# MCU.net
KiCad netlist of a schematic drawn in Altium Designer
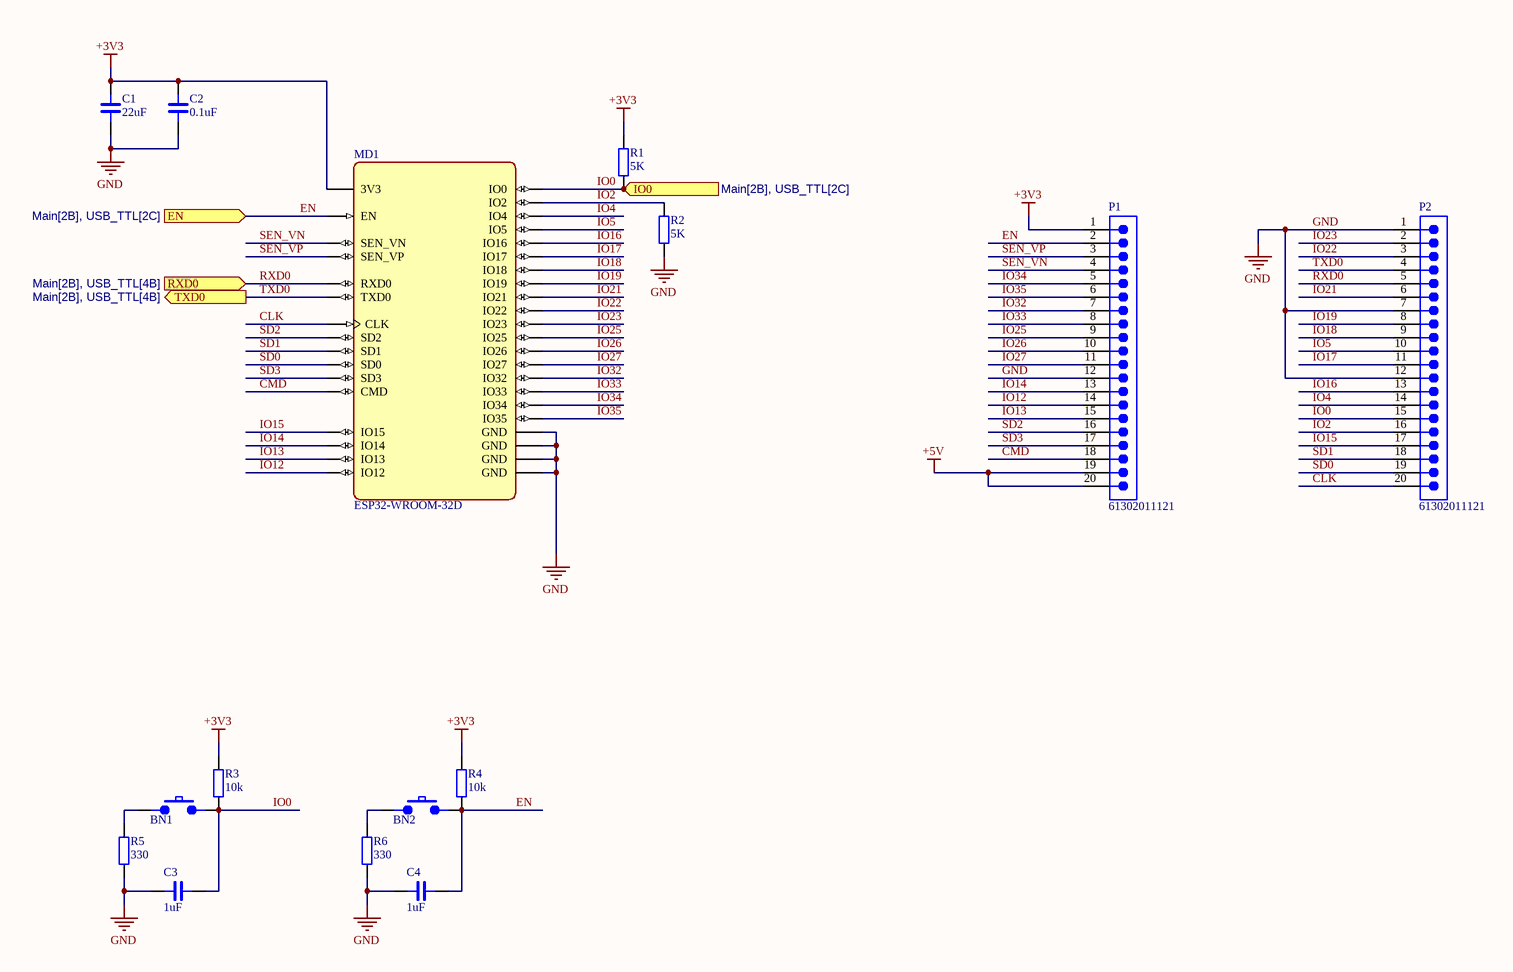
[diagram p0: MCU.SchDoc]

(export (version "E")
  (design (tool "Eeschema 10.0.6"))
  (components
    (comp (ref "BN1")
      (value "SKRPABE010")
      (footprint "BTN_SKRPABE010")
      (description "3.2mm 2.5mm button 50mA Brick SPST 16V SMD Tactile Switches")
      (fields (field (name "JLCPCB PART") "?"))
      (libsource (lib "FIC_OAL") (part "BTN_SKRPABE010"))
    )
    (comp (ref "BN2")
      (value "SKRPABE010")
      (footprint "BTN_SKRPABE010")
      (description "3.2mm 2.5mm button 50mA Brick SPST 16V SMD Tactile Switches")
      (fields (field (name "JLCPCB PART") "?"))
      (libsource (lib "FIC_OAL") (part "BTN_SKRPABE010"))
    )
    (comp (ref "C1")
      (value "22uF")
      (footprint "CAP_0603")
      (description "0603 Multilayer Ceramic Capacitors MLCC - SMD/SMT ROHS")
      (fields (field (name "LCSC PART") "?"))
      (libsource (lib "FIC_OAL") (part "CAP_0603"))
    )
    (comp (ref "C2")
      (value "0.1uF")
      (footprint "CAP_0603")
      (description "0603 Multilayer Ceramic Capacitors MLCC - SMD/SMT ROHS")
      (fields (field (name "LCSC PART") "?"))
      (libsource (lib "FIC_OAL") (part "CAP_0603"))
    )
    (comp (ref "C3")
      (value "1uF")
      (footprint "CAP_0603")
      (description "0603 Multilayer Ceramic Capacitors MLCC - SMD/SMT ROHS")
      (fields (field (name "LCSC PART") "?"))
      (libsource (lib "FIC_OAL") (part "CAP_0603"))
    )
    (comp (ref "C4")
      (value "1uF")
      (footprint "CAP_0603")
      (description "0603 Multilayer Ceramic Capacitors MLCC - SMD/SMT ROHS")
      (fields (field (name "LCSC PART") "?"))
      (libsource (lib "FIC_OAL") (part "CAP_0603"))
    )
    (comp (ref "MD1")
      (value "ESP32-WROOM-32D")
      (footprint "MD_ESP32_WROOM_D")
      (description "core ESP32-D0WD, 32Mbits, 3.3V, 40Mhz, onboard antenna")
      (fields (field (name "MRF. PART") "?"))
      (libsource (lib "FIC_OAL") (part "MD_ESP32_WROOM_D"))
    )
    (comp (ref "P1")
      (value "61302011121")
      (footprint "61302011121")
      (libsource (lib "Altium Content Vault") (part "Header_Male_1R_20P"))
    )
    (comp (ref "P2")
      (value "61302011121")
      (footprint "61302011121")
      (libsource (lib "Altium Content Vault") (part "Header_Male_1R_20P"))
    )
    (comp (ref "R1")
      (value "5K")
      (footprint "RES_0603")
      (description "0603 Thick Film Resistor - Surface Mount ROHS")
      (fields (field (name "MFR. PART") "?"))
      (libsource (lib "FIC_OAL") (part "RES_0603"))
    )
    (comp (ref "R2")
      (value "5K")
      (footprint "RES_0603")
      (description "0603 Thick Film Resistor - Surface Mount ROHS")
      (fields (field (name "MFR. PART") "?"))
      (libsource (lib "FIC_OAL") (part "RES_0603"))
    )
    (comp (ref "R3")
      (value "10k")
      (footprint "RES_0603")
      (description "0603 Thick Film Resistor - Surface Mount ROHS")
      (fields (field (name "MFR. PART") "?"))
      (libsource (lib "FIC_OAL") (part "RES_0603"))
    )
    (comp (ref "R4")
      (value "10k")
      (footprint "RES_0603")
      (description "0603 Thick Film Resistor - Surface Mount ROHS")
      (fields (field (name "MFR. PART") "?"))
      (libsource (lib "FIC_OAL") (part "RES_0603"))
    )
    (comp (ref "R5")
      (value "330")
      (footprint "RES_0603")
      (description "0603 Thick Film Resistor - Surface Mount ROHS")
      (fields (field (name "MFR. PART") "?"))
      (libsource (lib "FIC_OAL") (part "RES_0603"))
    )
    (comp (ref "R6")
      (value "330")
      (footprint "RES_0603")
      (description "0603 Thick Film Resistor - Surface Mount ROHS")
      (fields (field (name "MFR. PART") "?"))
      (libsource (lib "FIC_OAL") (part "RES_0603"))
    )
  )
  (nets
    (net (code "1") (name "+3V3") (class "Default")
      (node (ref "C1") (pin "2") (pinfunction "2_2") (pintype "passive"))
      (node (ref "C2") (pin "2") (pinfunction "2_2") (pintype "passive"))
      (node (ref "MD1") (pin "2") (pinfunction "3V3_2") (pintype "passive"))
      (node (ref "P1") (pin "1") (pinfunction "1_1") (pintype "passive"))
      (node (ref "R1") (pin "2") (pinfunction "2_2") (pintype "passive"))
      (node (ref "R3") (pin "2") (pinfunction "2_2") (pintype "passive"))
      (node (ref "R4") (pin "2") (pinfunction "2_2") (pintype "passive"))
    )
    (net (code "2") (name "+5V") (class "Default")
      (node (ref "P1") (pin "19") (pinfunction "19_19") (pintype "passive"))
      (node (ref "P1") (pin "20") (pinfunction "20_20") (pintype "passive"))
    )
    (net (code "3") (name "/CLK") (class "Default")
      (node (ref "MD1") (pin "20") (pinfunction "CLK_20") (pintype "input"))
      (node (ref "P2") (pin "20") (pinfunction "20_20") (pintype "passive"))
    )
    (net (code "4") (name "/CMD") (class "Default")
      (node (ref "MD1") (pin "19") (pinfunction "CMD_19") (pintype "bidirectional"))
      (node (ref "P1") (pin "18") (pinfunction "18_18") (pintype "passive"))
    )
    (net (code "5") (name "/EN") (class "Default")
      (node (ref "BN2") (pin "34") (pinfunction "34_34") (pintype "passive"))
      (node (ref "C4") (pin "2") (pinfunction "2_2") (pintype "passive"))
      (node (ref "MD1") (pin "3") (pinfunction "EN_3") (pintype "input"))
      (node (ref "P1") (pin "2") (pinfunction "2_2") (pintype "passive"))
      (node (ref "R4") (pin "1") (pinfunction "1_1") (pintype "passive"))
    )
    (net (code "6") (name "/IO0") (class "Default")
      (node (ref "BN1") (pin "34") (pinfunction "34_34") (pintype "passive"))
      (node (ref "C3") (pin "2") (pinfunction "2_2") (pintype "passive"))
      (node (ref "MD1") (pin "25") (pinfunction "IO0_25") (pintype "bidirectional"))
      (node (ref "P2") (pin "15") (pinfunction "15_15") (pintype "passive"))
      (node (ref "R1") (pin "1") (pinfunction "1_1") (pintype "passive"))
      (node (ref "R3") (pin "1") (pinfunction "1_1") (pintype "passive"))
    )
    (net (code "7") (name "/IO2") (class "Default")
      (node (ref "MD1") (pin "24") (pinfunction "IO2_24") (pintype "bidirectional"))
      (node (ref "P2") (pin "16") (pinfunction "16_16") (pintype "passive"))
      (node (ref "R2") (pin "2") (pinfunction "2_2") (pintype "passive"))
    )
    (net (code "8") (name "/IO4") (class "Default")
      (node (ref "MD1") (pin "26") (pinfunction "IO4_26") (pintype "bidirectional"))
      (node (ref "P2") (pin "14") (pinfunction "14_14") (pintype "passive"))
    )
    (net (code "9") (name "/IO5") (class "Default")
      (node (ref "MD1") (pin "29") (pinfunction "IO5_29") (pintype "bidirectional"))
      (node (ref "P2") (pin "10") (pinfunction "10_10") (pintype "passive"))
    )
    (net (code "10") (name "/IO12") (class "Default")
      (node (ref "MD1") (pin "14") (pinfunction "IO12_14") (pintype "bidirectional"))
      (node (ref "P1") (pin "14") (pinfunction "14_14") (pintype "passive"))
    )
    (net (code "11") (name "/IO13") (class "Default")
      (node (ref "MD1") (pin "16") (pinfunction "IO13_16") (pintype "bidirectional"))
      (node (ref "P1") (pin "15") (pinfunction "15_15") (pintype "passive"))
    )
    (net (code "12") (name "/IO14") (class "Default")
      (node (ref "MD1") (pin "13") (pinfunction "IO14_13") (pintype "bidirectional"))
      (node (ref "P1") (pin "13") (pinfunction "13_13") (pintype "passive"))
    )
    (net (code "13") (name "/IO15") (class "Default")
      (node (ref "MD1") (pin "23") (pinfunction "IO15_23") (pintype "bidirectional"))
      (node (ref "P2") (pin "17") (pinfunction "17_17") (pintype "passive"))
    )
    (net (code "14") (name "/IO16") (class "Default")
      (node (ref "MD1") (pin "27") (pinfunction "IO16_27") (pintype "bidirectional"))
      (node (ref "P2") (pin "13") (pinfunction "13_13") (pintype "passive"))
    )
    (net (code "15") (name "/IO17") (class "Default")
      (node (ref "MD1") (pin "28") (pinfunction "IO17_28") (pintype "bidirectional"))
      (node (ref "P2") (pin "11") (pinfunction "11_11") (pintype "passive"))
    )
    (net (code "16") (name "/IO18") (class "Default")
      (node (ref "MD1") (pin "30") (pinfunction "IO18_30") (pintype "bidirectional"))
      (node (ref "P2") (pin "9") (pinfunction "9_9") (pintype "passive"))
    )
    (net (code "17") (name "/IO19") (class "Default")
      (node (ref "MD1") (pin "31") (pinfunction "IO19_31") (pintype "bidirectional"))
      (node (ref "P2") (pin "8") (pinfunction "8_8") (pintype "passive"))
    )
    (net (code "18") (name "/IO21") (class "Default")
      (node (ref "MD1") (pin "33") (pinfunction "IO21_33") (pintype "bidirectional"))
      (node (ref "P2") (pin "6") (pinfunction "6_6") (pintype "passive"))
    )
    (net (code "19") (name "/IO22") (class "Default")
      (node (ref "MD1") (pin "36") (pinfunction "IO22_36") (pintype "bidirectional"))
      (node (ref "P2") (pin "3") (pinfunction "3_3") (pintype "passive"))
    )
    (net (code "20") (name "/IO23") (class "Default")
      (node (ref "MD1") (pin "37") (pinfunction "IO23_37") (pintype "bidirectional"))
      (node (ref "P2") (pin "2") (pinfunction "2_2") (pintype "passive"))
    )
    (net (code "21") (name "/IO25") (class "Default")
      (node (ref "MD1") (pin "10") (pinfunction "IO25_10") (pintype "bidirectional"))
      (node (ref "P1") (pin "9") (pinfunction "9_9") (pintype "passive"))
    )
    (net (code "22") (name "/IO26") (class "Default")
      (node (ref "MD1") (pin "11") (pinfunction "IO26_11") (pintype "bidirectional"))
      (node (ref "P1") (pin "10") (pinfunction "10_10") (pintype "passive"))
    )
    (net (code "23") (name "/IO27") (class "Default")
      (node (ref "MD1") (pin "12") (pinfunction "IO27_12") (pintype "bidirectional"))
      (node (ref "P1") (pin "11") (pinfunction "11_11") (pintype "passive"))
    )
    (net (code "24") (name "/IO32") (class "Default")
      (node (ref "MD1") (pin "8") (pinfunction "IO32_8") (pintype "bidirectional"))
      (node (ref "P1") (pin "7") (pinfunction "7_7") (pintype "passive"))
    )
    (net (code "25") (name "/IO33") (class "Default")
      (node (ref "MD1") (pin "9") (pinfunction "IO33_9") (pintype "bidirectional"))
      (node (ref "P1") (pin "8") (pinfunction "8_8") (pintype "passive"))
    )
    (net (code "26") (name "/IO34") (class "Default")
      (node (ref "MD1") (pin "6") (pinfunction "IO34_6") (pintype "bidirectional"))
      (node (ref "P1") (pin "5") (pinfunction "5_5") (pintype "passive"))
    )
    (net (code "27") (name "/IO35") (class "Default")
      (node (ref "MD1") (pin "7") (pinfunction "IO35_7") (pintype "bidirectional"))
      (node (ref "P1") (pin "6") (pinfunction "6_6") (pintype "passive"))
    )
    (net (code "28") (name "/RXD0") (class "Default")
      (node (ref "MD1") (pin "34") (pinfunction "RXD0_34") (pintype "bidirectional"))
      (node (ref "P2") (pin "5") (pinfunction "5_5") (pintype "passive"))
    )
    (net (code "29") (name "/SD0") (class "Default")
      (node (ref "MD1") (pin "21") (pinfunction "SD0_21") (pintype "bidirectional"))
      (node (ref "P2") (pin "19") (pinfunction "19_19") (pintype "passive"))
    )
    (net (code "30") (name "/SD1") (class "Default")
      (node (ref "MD1") (pin "22") (pinfunction "SD1_22") (pintype "bidirectional"))
      (node (ref "P2") (pin "18") (pinfunction "18_18") (pintype "passive"))
    )
    (net (code "31") (name "/SD2") (class "Default")
      (node (ref "MD1") (pin "17") (pinfunction "SD2_17") (pintype "bidirectional"))
      (node (ref "P1") (pin "16") (pinfunction "16_16") (pintype "passive"))
    )
    (net (code "32") (name "/SD3") (class "Default")
      (node (ref "MD1") (pin "18") (pinfunction "SD3_18") (pintype "bidirectional"))
      (node (ref "P1") (pin "17") (pinfunction "17_17") (pintype "passive"))
    )
    (net (code "33") (name "/SEN_VN") (class "Default")
      (node (ref "MD1") (pin "5") (pinfunction "SEN_VN_5") (pintype "bidirectional"))
      (node (ref "P1") (pin "4") (pinfunction "4_4") (pintype "passive"))
    )
    (net (code "34") (name "/SEN_VP") (class "Default")
      (node (ref "MD1") (pin "4") (pinfunction "SEN_VP_4") (pintype "bidirectional"))
      (node (ref "P1") (pin "3") (pinfunction "3_3") (pintype "passive"))
    )
    (net (code "35") (name "/TXD0") (class "Default")
      (node (ref "MD1") (pin "35") (pinfunction "TXD0_35") (pintype "bidirectional"))
      (node (ref "P2") (pin "4") (pinfunction "4_4") (pintype "passive"))
    )
    (net (code "36") (name "GND") (class "Default")
      (node (ref "C1") (pin "1") (pinfunction "1_1") (pintype "passive"))
      (node (ref "C2") (pin "1") (pinfunction "1_1") (pintype "passive"))
      (node (ref "C3") (pin "1") (pinfunction "1_1") (pintype "passive"))
      (node (ref "C4") (pin "1") (pinfunction "1_1") (pintype "passive"))
      (node (ref "MD1") (pin "1") (pinfunction "GND_1") (pintype "passive"))
      (node (ref "MD1") (pin "15") (pinfunction "GND_15") (pintype "power_in"))
      (node (ref "MD1") (pin "38") (pinfunction "GND_38") (pintype "power_in"))
      (node (ref "MD1") (pin "39") (pinfunction "GND_39") (pintype "power_in"))
      (node (ref "P1") (pin "12") (pinfunction "12_12") (pintype "passive"))
      (node (ref "P2") (pin "1") (pinfunction "1_1") (pintype "passive"))
      (node (ref "P2") (pin "12") (pinfunction "12_12") (pintype "passive"))
      (node (ref "P2") (pin "7") (pinfunction "7_7") (pintype "passive"))
      (node (ref "R2") (pin "1") (pinfunction "1_1") (pintype "passive"))
      (node (ref "R5") (pin "1") (pinfunction "1_1") (pintype "passive"))
      (node (ref "R6") (pin "1") (pinfunction "1_1") (pintype "passive"))
    )
    (net (code "37") (name "Net-(BN1-Pad12)") (class "Default")
      (node (ref "BN1") (pin "12") (pinfunction "12_12") (pintype "passive"))
      (node (ref "R5") (pin "2") (pinfunction "2_2") (pintype "passive"))
    )
    (net (code "38") (name "Net-(BN2-Pad12)") (class "Default")
      (node (ref "BN2") (pin "12") (pinfunction "12_12") (pintype "passive"))
      (node (ref "R6") (pin "2") (pinfunction "2_2") (pintype "passive"))
    )
  )
)
